# ZF.net
KiCad netlist of a schematic drawn in Altium Designer
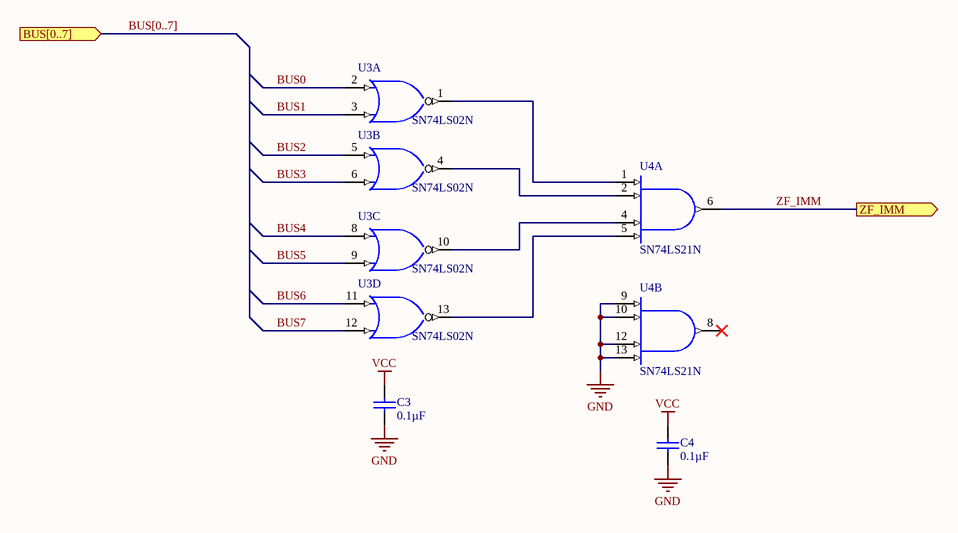
[diagram p0: ZF.SchDoc]

(export (version "E")
  (design (tool "Eeschema 10.0.6"))
  (components
    (comp (ref "C3")
      (value "K104K15X7RF5TL2")
      (footprint "VISH-K104K15X7RF5TL2")
      (description "Ceramic Capacitor, 100 nF, +/- 10%, 50 V, -55 to 125 degC, 2-Pin THD, RoHS, Tape and Reel")
      (fields
        (field (name "MANUFACTURER") "Vishay")
        (field (name "TOLERANCE") "±10%")
        (field (name "CAPACITANCE") "0.1µF")
      )
      (libsource (lib "Altium Content Vault") (part "CAP-NP-2"))
    )
    (comp (ref "C4")
      (value "K104K15X7RF5TL2")
      (footprint "VISH-K104K15X7RF5TL2")
      (description "Ceramic Capacitor, 100 nF, +/- 10%, 50 V, -55 to 125 degC, 2-Pin THD, RoHS, Tape and Reel")
      (fields
        (field (name "MANUFACTURER") "Vishay")
        (field (name "TOLERANCE") "±10%")
        (field (name "CAPACITANCE") "0.1µF")
      )
      (libsource (lib "Altium Content Vault") (part "CAP-NP-2"))
    )
    (comp (ref "U3")
      (value "SN74LS02N")
      (footprint "N014")
      (description "Quadruple 2-Input Positive-NOR Gate")
      (fields (field (name "PUBLISHER") "Altium Limited"))
      (libsource (lib "TI Logic Gate 2") (part "SN74LS02N"))
    )
    (comp (ref "U4")
      (value "SN74LS21N")
      (footprint "N014")
      (description "Dual 4-Input Positive-AND Gate")
      (fields (field (name "PUBLISHER") "Altium Limited"))
      (libsource (lib "TI Logic Gate 2") (part "SN74LS21N"))
    )
  )
  (nets
    (net (code "1") (name "/BUS0") (class "Default")
      (node (ref "U3") (pin "2") (pinfunction "A_2") (pintype "input"))
    )
    (net (code "2") (name "/BUS1") (class "Default")
      (node (ref "U3") (pin "3") (pinfunction "B_3") (pintype "input"))
    )
    (net (code "3") (name "/BUS2") (class "Default")
      (node (ref "U3") (pin "5") (pinfunction "A_5") (pintype "input"))
    )
    (net (code "4") (name "/BUS3") (class "Default")
      (node (ref "U3") (pin "6") (pinfunction "B_6") (pintype "input"))
    )
    (net (code "5") (name "/BUS4") (class "Default")
      (node (ref "U3") (pin "8") (pinfunction "A_8") (pintype "input"))
    )
    (net (code "6") (name "/BUS5") (class "Default")
      (node (ref "U3") (pin "9") (pinfunction "B_9") (pintype "input"))
    )
    (net (code "7") (name "/BUS6") (class "Default")
      (node (ref "U3") (pin "11") (pinfunction "A_11") (pintype "input"))
    )
    (net (code "8") (name "/BUS7") (class "Default")
      (node (ref "U3") (pin "12") (pinfunction "B_12") (pintype "input"))
    )
    (net (code "10") (name "/ZF_IMM") (class "Default")
      (node (ref "U4") (pin "6") (pinfunction "Y_6") (pintype "output"))
    )
    (net (code "11") (name "GND") (class "Default")
      (node (ref "C3") (pin "2") (pinfunction "2_2") (pintype "passive"))
      (node (ref "C4") (pin "2") (pinfunction "2_2") (pintype "passive"))
      (node (ref "U3") (pin "7") (pinfunction "GND_7") (pintype "power_in"))
      (node (ref "U4") (pin "10") (pinfunction "B_10") (pintype "input"))
      (node (ref "U4") (pin "12") (pinfunction "C_12") (pintype "input"))
      (node (ref "U4") (pin "13") (pinfunction "D_13") (pintype "input"))
      (node (ref "U4") (pin "7") (pinfunction "GND_7") (pintype "power_in"))
      (node (ref "U4") (pin "9") (pinfunction "A_9") (pintype "input"))
    )
    (net (code "12") (name "Net-(U3A-Y)") (class "Default")
      (node (ref "U3") (pin "1") (pinfunction "Y_1") (pintype "output"))
      (node (ref "U4") (pin "1") (pinfunction "A_1") (pintype "input"))
    )
    (net (code "13") (name "Net-(U3B-Y)") (class "Default")
      (node (ref "U3") (pin "4") (pinfunction "Y_4") (pintype "output"))
      (node (ref "U4") (pin "2") (pinfunction "B_2") (pintype "input"))
    )
    (net (code "14") (name "Net-(U3C-Y)") (class "Default")
      (node (ref "U3") (pin "10") (pinfunction "Y_10") (pintype "output"))
      (node (ref "U4") (pin "4") (pinfunction "C_4") (pintype "input"))
    )
    (net (code "15") (name "Net-(U3D-Y)") (class "Default")
      (node (ref "U3") (pin "13") (pinfunction "Y_13") (pintype "output"))
      (node (ref "U4") (pin "5") (pinfunction "D_5") (pintype "input"))
    )
    (net (code "16") (name "VCC") (class "Default")
      (node (ref "C3") (pin "1") (pinfunction "1_1") (pintype "passive"))
      (node (ref "C4") (pin "1") (pinfunction "1_1") (pintype "passive"))
      (node (ref "U3") (pin "14") (pinfunction "VCC_14") (pintype "power_in"))
      (node (ref "U4") (pin "14") (pinfunction "VCC_14") (pintype "power_in"))
    )
    (net (code "17") (name "unconnected-(U4B-Y-Pad8)") (class "Default")
      (node (ref "U4") (pin "8") (pinfunction "Y_8") (pintype "output+no_connect"))
    )
  )
)
